# ihc_mon.net
KiCad netlist of a schematic drawn in EAGLE
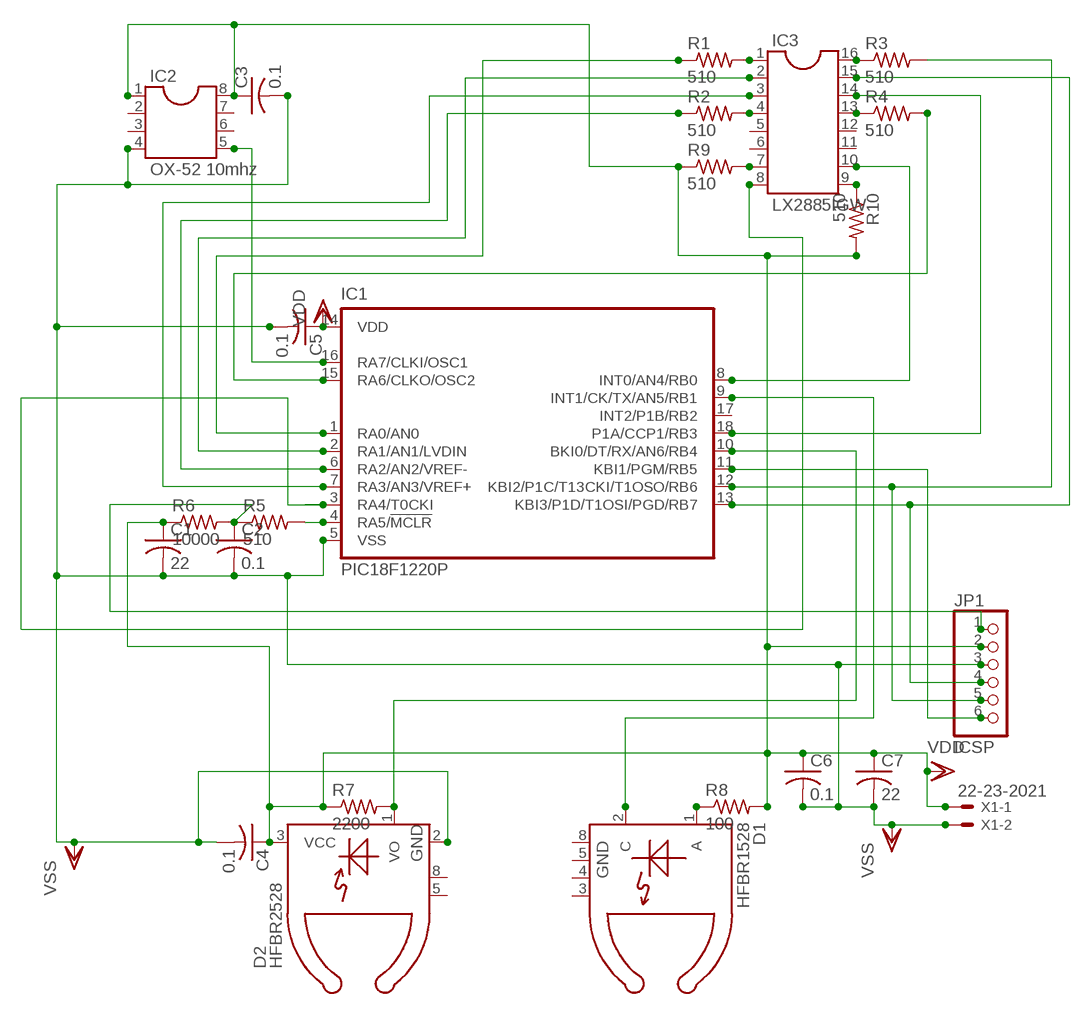
[diagram p0: schematic, sheet 1]

(export (version "E")
  (design (tool "Eeschema 10.0.6"))
  (components
    (comp (ref "C1")
      (value "22")
      (footprint "eagle-import:C025-024X044")
      (libsource (lib "eagle-import") (part "C-US025-024X044"))
    )
    (comp (ref "C2")
      (value "0.1")
      (footprint "eagle-import:C050-025X075")
      (libsource (lib "eagle-import") (part "C-US050-025X075"))
    )
    (comp (ref "C3")
      (value "0.1")
      (footprint "eagle-import:C050-025X075")
      (libsource (lib "eagle-import") (part "C-US050-025X075"))
    )
    (comp (ref "C4")
      (value "0.1")
      (footprint "eagle-import:C050-025X075")
      (libsource (lib "eagle-import") (part "C-US050-025X075"))
    )
    (comp (ref "C5")
      (value "0.1")
      (footprint "eagle-import:C050-025X075")
      (libsource (lib "eagle-import") (part "C-US050-025X075"))
    )
    (comp (ref "C6")
      (value "0.1")
      (footprint "eagle-import:C050-025X075")
      (libsource (lib "eagle-import") (part "C-US050-025X075"))
    )
    (comp (ref "C7")
      (value "22")
      (footprint "eagle-import:C025-024X044")
      (libsource (lib "eagle-import") (part "C-US025-024X044"))
    )
    (comp (ref "D1")
      (value "HFBR1528")
      (footprint "eagle-import:HFBR25XX")
      (fields (field (name "MF") "AGILENT TECHNOLOGIES") (field (name "MPN") "HFBR-1528"))
      (libsource (lib "eagle-import") (part "HFBR1528"))
    )
    (comp (ref "D2")
      (value "HFBR2528")
      (footprint "eagle-import:HFBR25XX")
      (fields (field (name "MF") "AGILENT TECHNOLOGIES") (field (name "MPN") "HFBR-2528"))
      (libsource (lib "eagle-import") (part "HFBR2528"))
    )
    (comp (ref "IC1")
      (value "PIC18F1220P")
      (footprint "eagle-import:DIL18")
      (fields (field (name "MF") "MICROCHIP") (field (name "MPN") "PIC18F1220-I/P"))
      (libsource (lib "eagle-import") (part "PIC18F120P2"))
    )
    (comp (ref "IC2")
      (value "OX-52 10mhz")
      (footprint "eagle-import:SOCKET-08")
      (libsource (lib "eagle-import") (part "DIL8S"))
    )
    (comp (ref "IC3")
      (value "LX2885IGW")
      (footprint "eagle-import:SOCKET-16")
      (libsource (lib "eagle-import") (part "DIL16S"))
    )
    (comp (ref "JP1")
      (value "ICSP")
      (footprint "eagle-import:1X06")
      (libsource (lib "eagle-import") (part "PINHD-1X6"))
    )
    (comp (ref "R1")
      (value "510")
      (footprint "eagle-import:0204V")
      (libsource (lib "eagle-import") (part "R-US_0204/2V"))
    )
    (comp (ref "R2")
      (value "510")
      (footprint "eagle-import:0204V")
      (libsource (lib "eagle-import") (part "R-US_0204/2V"))
    )
    (comp (ref "R3")
      (value "510")
      (footprint "eagle-import:0204V")
      (libsource (lib "eagle-import") (part "R-US_0204/2V"))
    )
    (comp (ref "R4")
      (value "510")
      (footprint "eagle-import:0204V")
      (libsource (lib "eagle-import") (part "R-US_0204/2V"))
    )
    (comp (ref "R5")
      (value "510")
      (footprint "eagle-import:0204V")
      (libsource (lib "eagle-import") (part "R-US_0204/2V"))
    )
    (comp (ref "R6")
      (value "10000")
      (footprint "eagle-import:0204V")
      (libsource (lib "eagle-import") (part "R-US_0204/2V"))
    )
    (comp (ref "R7")
      (value "2200")
      (footprint "eagle-import:0204V")
      (libsource (lib "eagle-import") (part "R-US_0204/2V"))
    )
    (comp (ref "R8")
      (value "100")
      (footprint "eagle-import:0204V")
      (libsource (lib "eagle-import") (part "R-US_0204/2V"))
    )
    (comp (ref "R9")
      (value "510")
      (footprint "eagle-import:0204V")
      (libsource (lib "eagle-import") (part "R-US_0204/2V"))
    )
    (comp (ref "R10")
      (value "510")
      (footprint "eagle-import:0204V")
      (libsource (lib "eagle-import") (part "R-US_0204/2V"))
    )
    (comp (ref "X1")
      (value "22-23-2021")
      (footprint "eagle-import:22-23-2021")
      (fields (field (name "MF") "MOLEX"))
      (libsource (lib "eagle-import") (part "22-23-2021"))
    )
  )
  (nets
    (net (code "1") (name "Net-(C2-Pad1)") (class "Default")
      (node (ref "C2") (pin "1") (pinfunction "1_1") (pintype "passive"))
      (node (ref "JP1") (pin "1") (pinfunction "1_1") (pintype "passive"))
      (node (ref "R5") (pin "1") (pinfunction "1_1") (pintype "passive"))
      (node (ref "R6") (pin "2") (pinfunction "2_2") (pintype "passive"))
    )
    (net (code "2") (name "Net-(D1-A)") (class "Default")
      (node (ref "D1") (pin "1") (pinfunction "A_1") (pintype "passive"))
      (node (ref "R8") (pin "1") (pinfunction "1_1") (pintype "passive"))
    )
    (net (code "3") (name "Net-(D1-C)") (class "Default")
      (node (ref "D1") (pin "2") (pinfunction "C_2") (pintype "passive"))
      (node (ref "IC1") (pin "9") (pinfunction "INT1/CK/TX/AN5/RB1_9") (pintype "bidirectional"))
    )
    (net (code "4") (name "Net-(D2-VO)") (class "Default")
      (node (ref "D2") (pin "1") (pinfunction "VO_1") (pintype "output"))
      (node (ref "IC1") (pin "10") (pinfunction "BKI0/DT/RX/AN6/RB4_10") (pintype "bidirectional"))
      (node (ref "R7") (pin "2") (pinfunction "2_2") (pintype "passive"))
    )
    (net (code "5") (name "Net-(IC1-INT0{slash}AN4{slash}RB0)") (class "Default")
      (node (ref "IC1") (pin "8") (pinfunction "INT0/AN4/RB0_8") (pintype "bidirectional"))
      (node (ref "IC3") (pin "10") (pinfunction "10_10") (pintype "passive"))
    )
    (net (code "6") (name "Net-(IC1-KBI1{slash}PGM{slash}RB5)") (class "Default")
      (node (ref "IC1") (pin "11") (pinfunction "KBI1/PGM/RB5_11") (pintype "bidirectional"))
      (node (ref "JP1") (pin "6") (pinfunction "6_6") (pintype "passive"))
    )
    (net (code "7") (name "Net-(IC1-KBI2{slash}P1C{slash}T13CKI{slash}T1OSO{slash}RB6)") (class "Default")
      (node (ref "IC1") (pin "12") (pinfunction "KBI2/P1C/T13CKI/T1OSO/RB6_12") (pintype "bidirectional"))
      (node (ref "JP1") (pin "5") (pinfunction "5_5") (pintype "passive"))
      (node (ref "R3") (pin "2") (pinfunction "2_2") (pintype "passive"))
    )
    (net (code "8") (name "Net-(IC1-KBI3{slash}P1D{slash}T1OSI{slash}PGD{slash}RB7)") (class "Default")
      (node (ref "IC1") (pin "13") (pinfunction "KBI3/P1D/T1OSI/PGD/RB7_13") (pintype "bidirectional"))
      (node (ref "IC3") (pin "15") (pinfunction "15_15") (pintype "passive"))
      (node (ref "JP1") (pin "4") (pinfunction "4_4") (pintype "passive"))
    )
    (net (code "9") (name "Net-(IC1-P1A{slash}CCP1{slash}RB3)") (class "Default")
      (node (ref "IC1") (pin "18") (pinfunction "P1A/CCP1/RB3_18") (pintype "bidirectional"))
      (node (ref "IC3") (pin "14") (pinfunction "14_14") (pintype "passive"))
    )
    (net (code "10") (name "Net-(IC1-RA0{slash}AN0)") (class "Default")
      (node (ref "IC1") (pin "1") (pinfunction "RA0/AN0_1") (pintype "bidirectional"))
      (node (ref "R1") (pin "1") (pinfunction "1_1") (pintype "passive"))
    )
    (net (code "11") (name "Net-(IC1-RA1{slash}AN1{slash}LVDIN)") (class "Default")
      (node (ref "IC1") (pin "2") (pinfunction "RA1/AN1/LVDIN_2") (pintype "bidirectional"))
      (node (ref "IC3") (pin "2") (pinfunction "2_2") (pintype "passive"))
    )
    (net (code "12") (name "Net-(IC1-RA2{slash}AN2{slash}VREF-)") (class "Default")
      (node (ref "IC1") (pin "6") (pinfunction "RA2/AN2/VREF-_6") (pintype "bidirectional"))
      (node (ref "R2") (pin "1") (pinfunction "1_1") (pintype "passive"))
    )
    (net (code "13") (name "Net-(IC1-RA3{slash}AN3{slash}VREF+)") (class "Default")
      (node (ref "IC1") (pin "7") (pinfunction "RA3/AN3/VREF+_7") (pintype "bidirectional"))
      (node (ref "IC3") (pin "3") (pinfunction "3_3") (pintype "passive"))
    )
    (net (code "14") (name "Net-(IC1-RA4{slash}T0CKI)") (class "Default")
      (node (ref "IC1") (pin "3") (pinfunction "RA4/T0CKI_3") (pintype "bidirectional"))
      (node (ref "IC3") (pin "8") (pinfunction "8_8") (pintype "passive"))
    )
    (net (code "15") (name "Net-(IC1-RA5{slash}~{MCLR})") (class "Default")
      (node (ref "IC1") (pin "4") (pinfunction "RA5/~{MCLR}_4") (pintype "input"))
      (node (ref "R5") (pin "2") (pinfunction "2_2") (pintype "passive"))
    )
    (net (code "16") (name "Net-(IC1-RA6{slash}CLKO{slash}OSC2)") (class "Default")
      (node (ref "IC1") (pin "15") (pinfunction "RA6/CLKO/OSC2_15") (pintype "bidirectional"))
      (node (ref "R4") (pin "2") (pinfunction "2_2") (pintype "passive"))
    )
    (net (code "17") (name "Net-(IC1-RA7{slash}CLKI{slash}OSC1)") (class "Default")
      (node (ref "IC1") (pin "16") (pinfunction "RA7/CLKI/OSC1_16") (pintype "bidirectional"))
      (node (ref "IC2") (pin "5") (pinfunction "5_5") (pintype "passive"))
    )
    (net (code "18") (name "Net-(IC3-Pad1)") (class "Default")
      (node (ref "IC3") (pin "1") (pinfunction "1_1") (pintype "passive"))
      (node (ref "R1") (pin "2") (pinfunction "2_2") (pintype "passive"))
    )
    (net (code "19") (name "Net-(IC3-Pad4)") (class "Default")
      (node (ref "IC3") (pin "4") (pinfunction "4_4") (pintype "passive"))
      (node (ref "R2") (pin "2") (pinfunction "2_2") (pintype "passive"))
    )
    (net (code "20") (name "Net-(IC3-Pad7)") (class "Default")
      (node (ref "IC3") (pin "7") (pinfunction "7_7") (pintype "passive"))
      (node (ref "R9") (pin "2") (pinfunction "2_2") (pintype "passive"))
    )
    (net (code "21") (name "Net-(IC3-Pad9)") (class "Default")
      (node (ref "IC3") (pin "9") (pinfunction "9_9") (pintype "passive"))
      (node (ref "R10") (pin "1") (pinfunction "1_1") (pintype "passive"))
    )
    (net (code "22") (name "Net-(IC3-Pad13)") (class "Default")
      (node (ref "IC3") (pin "13") (pinfunction "13_13") (pintype "passive"))
      (node (ref "R4") (pin "1") (pinfunction "1_1") (pintype "passive"))
    )
    (net (code "23") (name "Net-(IC3-Pad16)") (class "Default")
      (node (ref "IC3") (pin "16") (pinfunction "16_16") (pintype "passive"))
      (node (ref "R3") (pin "1") (pinfunction "1_1") (pintype "passive"))
    )
    (net (code "24") (name "VDD") (class "Default")
      (node (ref "C1") (pin "1") (pinfunction "1_1") (pintype "passive"))
      (node (ref "C3") (pin "1") (pinfunction "1_1") (pintype "passive"))
      (node (ref "C4") (pin "1") (pinfunction "1_1") (pintype "passive"))
      (node (ref "C5") (pin "1") (pinfunction "1_1") (pintype "passive"))
      (node (ref "C6") (pin "1") (pinfunction "1_1") (pintype "passive"))
      (node (ref "C7") (pin "1") (pinfunction "1_1") (pintype "passive"))
      (node (ref "D2") (pin "3") (pinfunction "VCC_3") (pintype "passive"))
      (node (ref "IC1") (pin "14") (pinfunction "VDD_14") (pintype "power_in"))
      (node (ref "IC2") (pin "1") (pinfunction "1_1") (pintype "passive"))
      (node (ref "IC2") (pin "8") (pinfunction "8_8") (pintype "passive"))
      (node (ref "JP1") (pin "2") (pinfunction "2_2") (pintype "passive"))
      (node (ref "R10") (pin "2") (pinfunction "2_2") (pintype "passive"))
      (node (ref "R6") (pin "1") (pinfunction "1_1") (pintype "passive"))
      (node (ref "R7") (pin "1") (pinfunction "1_1") (pintype "passive"))
      (node (ref "R8") (pin "2") (pinfunction "2_2") (pintype "passive"))
      (node (ref "R9") (pin "1") (pinfunction "1_1") (pintype "passive"))
      (node (ref "X1") (pin "1") (pinfunction "S_1") (pintype "passive"))
    )
    (net (code "25") (name "VSS") (class "Default")
      (node (ref "C1") (pin "2") (pinfunction "2_2") (pintype "passive"))
      (node (ref "C2") (pin "2") (pinfunction "2_2") (pintype "passive"))
      (node (ref "C3") (pin "2") (pinfunction "2_2") (pintype "passive"))
      (node (ref "C4") (pin "2") (pinfunction "2_2") (pintype "passive"))
      (node (ref "C5") (pin "2") (pinfunction "2_2") (pintype "passive"))
      (node (ref "C6") (pin "2") (pinfunction "2_2") (pintype "passive"))
      (node (ref "C7") (pin "2") (pinfunction "2_2") (pintype "passive"))
      (node (ref "D2") (pin "2") (pinfunction "GND_2") (pintype "passive"))
      (node (ref "IC1") (pin "5") (pinfunction "VSS_5") (pintype "power_in"))
      (node (ref "IC2") (pin "4") (pinfunction "4_4") (pintype "passive"))
      (node (ref "JP1") (pin "3") (pinfunction "3_3") (pintype "passive"))
      (node (ref "X1") (pin "2") (pinfunction "S_2") (pintype "passive"))
    )
    (net (code "26") (name "unconnected-(D1-1-Pad3)") (class "Default")
      (node (ref "D1") (pin "3") (pinfunction "1_3") (pintype "passive"))
    )
    (net (code "27") (name "unconnected-(D1-GND-Pad5)") (class "Default")
      (node (ref "D1") (pin "5") (pinfunction "GND_5") (pintype "passive"))
    )
    (net (code "28") (name "unconnected-(D1-GND-Pad8)") (class "Default")
      (node (ref "D1") (pin "8") (pinfunction "GND_8") (pintype "passive"))
    )
    (net (code "29") (name "unconnected-(D1-Pad4)") (class "Default")
      (node (ref "D1") (pin "4") (pinfunction "4_4") (pintype "passive"))
    )
    (net (code "30") (name "unconnected-(D2-1-Pad5)") (class "Default")
      (node (ref "D2") (pin "5") (pinfunction "1_5") (pintype "passive"))
    )
    (net (code "31") (name "unconnected-(D2-4-Pad8)") (class "Default")
      (node (ref "D2") (pin "8") (pinfunction "4_8") (pintype "passive"))
    )
    (net (code "32") (name "unconnected-(IC1-INT2{slash}P1B{slash}RB2-Pad17)") (class "Default")
      (node (ref "IC1") (pin "17") (pinfunction "INT2/P1B/RB2_17") (pintype "bidirectional"))
    )
    (net (code "33") (name "unconnected-(IC2-Pad2)") (class "Default")
      (node (ref "IC2") (pin "2") (pinfunction "2_2") (pintype "passive"))
    )
    (net (code "34") (name "unconnected-(IC2-Pad3)") (class "Default")
      (node (ref "IC2") (pin "3") (pinfunction "3_3") (pintype "passive"))
    )
    (net (code "35") (name "unconnected-(IC2-Pad6)") (class "Default")
      (node (ref "IC2") (pin "6") (pinfunction "6_6") (pintype "passive"))
    )
    (net (code "36") (name "unconnected-(IC2-Pad7)") (class "Default")
      (node (ref "IC2") (pin "7") (pinfunction "7_7") (pintype "passive"))
    )
    (net (code "37") (name "unconnected-(IC3-Pad5)") (class "Default")
      (node (ref "IC3") (pin "5") (pinfunction "5_5") (pintype "passive"))
    )
    (net (code "38") (name "unconnected-(IC3-Pad6)") (class "Default")
      (node (ref "IC3") (pin "6") (pinfunction "6_6") (pintype "passive"))
    )
    (net (code "39") (name "unconnected-(IC3-Pad11)") (class "Default")
      (node (ref "IC3") (pin "11") (pinfunction "11_11") (pintype "passive"))
    )
    (net (code "40") (name "unconnected-(IC3-Pad12)") (class "Default")
      (node (ref "IC3") (pin "12") (pinfunction "12_12") (pintype "passive"))
    )
  )
)
